# micro_amp.net
KiCad netlist of a schematic drawn in EAGLE
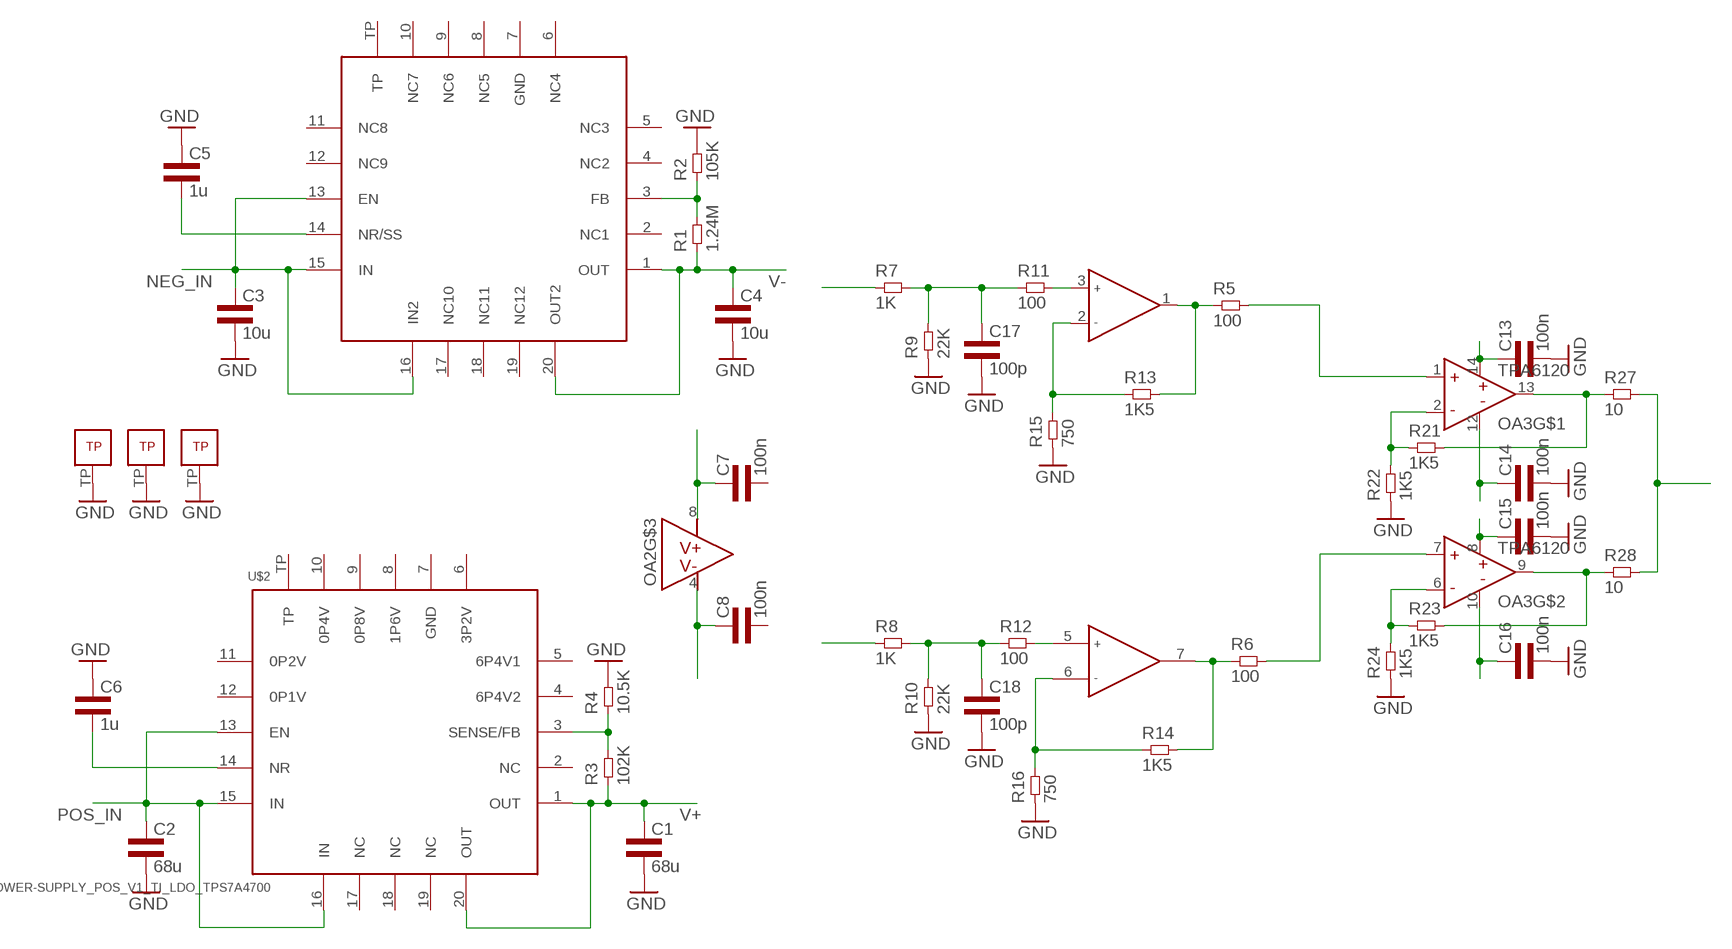
[diagram p0: schematic, sheet 1]

(export (version "E")
  (design (tool "Eeschema 10.0.6"))
  (components
    (comp (ref "C1")
      (value "68u")
      (footprint "eagle-import:1210L3")
      (libsource (lib "eagle-import") (part "CAP1210L3"))
    )
    (comp (ref "C2")
      (value "68u")
      (footprint "eagle-import:1210L3")
      (libsource (lib "eagle-import") (part "CAP1210L3"))
    )
    (comp (ref "C3")
      (value "10u")
      (footprint "eagle-import:0805L3")
      (libsource (lib "eagle-import") (part "CAP0805L3"))
    )
    (comp (ref "C4")
      (value "10u")
      (footprint "eagle-import:0805L3")
      (libsource (lib "eagle-import") (part "CAP0805L3"))
    )
    (comp (ref "C5")
      (value "1u")
      (footprint "eagle-import:0603L3")
      (libsource (lib "eagle-import") (part "CAP0603L3"))
    )
    (comp (ref "C6")
      (value "1u")
      (footprint "eagle-import:0603L3")
      (libsource (lib "eagle-import") (part "CAP0603L3"))
    )
    (comp (ref "C7")
      (value "100n")
      (footprint "eagle-import:0402L3")
      (libsource (lib "eagle-import") (part "CAP0402L3"))
    )
    (comp (ref "C8")
      (value "100n")
      (footprint "eagle-import:0402L3")
      (libsource (lib "eagle-import") (part "CAP0402L3"))
    )
    (comp (ref "C13")
      (value "100n")
      (footprint "eagle-import:0402L3")
      (libsource (lib "eagle-import") (part "CAP0402L3"))
    )
    (comp (ref "C14")
      (value "100n")
      (footprint "eagle-import:0402L3")
      (libsource (lib "eagle-import") (part "CAP0402L3"))
    )
    (comp (ref "C15")
      (value "100n")
      (footprint "eagle-import:0402L3")
      (libsource (lib "eagle-import") (part "CAP0402L3"))
    )
    (comp (ref "C16")
      (value "100n")
      (footprint "eagle-import:0402L3")
      (libsource (lib "eagle-import") (part "CAP0402L3"))
    )
    (comp (ref "C17")
      (value "100p")
      (footprint "eagle-import:0402L3")
      (libsource (lib "eagle-import") (part "CAP0402L3"))
    )
    (comp (ref "C18")
      (value "100p")
      (footprint "eagle-import:0402L3")
      (libsource (lib "eagle-import") (part "CAP0402L3"))
    )
    (comp (ref "OA1")
      (value "TPA6120QFN")
      (footprint "eagle-import:S-PVQFN-N14")
      (libsource (lib "eagle-import") (part "TPA6120QFN"))
    )
    (comp (ref "OA2")
      (value "OPA1612")
      (footprint "eagle-import:S-PWSON-N8")
      (libsource (lib "eagle-import") (part "OPA1612"))
    )
    (comp (ref "OA3")
      (value "TPA6120QFN")
      (footprint "eagle-import:S-PVQFN-N14")
      (libsource (lib "eagle-import") (part "TPA6120QFN"))
    )
    (comp (ref "R1")
      (value "1.24M")
      (footprint "eagle-import:0402L3")
      (libsource (lib "eagle-import") (part "RES0402L3"))
    )
    (comp (ref "R2")
      (value "105K")
      (footprint "eagle-import:0402L3")
      (libsource (lib "eagle-import") (part "RES0402L3"))
    )
    (comp (ref "R3")
      (value "102K")
      (footprint "eagle-import:0402L3")
      (libsource (lib "eagle-import") (part "RES0402L3"))
    )
    (comp (ref "R4")
      (value "10.5K")
      (footprint "eagle-import:0402L3")
      (libsource (lib "eagle-import") (part "RES0402L3"))
    )
    (comp (ref "R5")
      (value "100")
      (footprint "eagle-import:0402L3")
      (libsource (lib "eagle-import") (part "RES0402L3"))
    )
    (comp (ref "R6")
      (value "100")
      (footprint "eagle-import:0402L3")
      (libsource (lib "eagle-import") (part "RES0402L3"))
    )
    (comp (ref "R7")
      (value "1K")
      (footprint "eagle-import:0402L3")
      (libsource (lib "eagle-import") (part "RES0402L3"))
    )
    (comp (ref "R8")
      (value "1K")
      (footprint "eagle-import:0402L3")
      (libsource (lib "eagle-import") (part "RES0402L3"))
    )
    (comp (ref "R9")
      (value "22K")
      (footprint "eagle-import:0402L3")
      (libsource (lib "eagle-import") (part "RES0402L3"))
    )
    (comp (ref "R10")
      (value "22K")
      (footprint "eagle-import:0402L3")
      (libsource (lib "eagle-import") (part "RES0402L3"))
    )
    (comp (ref "R11")
      (value "100")
      (footprint "eagle-import:0402L3")
      (libsource (lib "eagle-import") (part "RES0402L3"))
    )
    (comp (ref "R12")
      (value "100")
      (footprint "eagle-import:0402L3")
      (libsource (lib "eagle-import") (part "RES0402L3"))
    )
    (comp (ref "R13")
      (value "1K5")
      (footprint "eagle-import:0402L3")
      (libsource (lib "eagle-import") (part "RES0402L3"))
    )
    (comp (ref "R14")
      (value "1K5")
      (footprint "eagle-import:0402L3")
      (libsource (lib "eagle-import") (part "RES0402L3"))
    )
    (comp (ref "R15")
      (value "750")
      (footprint "eagle-import:0402L3")
      (libsource (lib "eagle-import") (part "RES0402L3"))
    )
    (comp (ref "R16")
      (value "750")
      (footprint "eagle-import:0402L3")
      (libsource (lib "eagle-import") (part "RES0402L3"))
    )
    (comp (ref "R21")
      (value "1K5")
      (footprint "eagle-import:0402L3")
      (libsource (lib "eagle-import") (part "RES0402L3"))
    )
    (comp (ref "R22")
      (value "1K5")
      (footprint "eagle-import:0402L3")
      (libsource (lib "eagle-import") (part "RES0402L3"))
    )
    (comp (ref "R23")
      (value "1K5")
      (footprint "eagle-import:0402L3")
      (libsource (lib "eagle-import") (part "RES0402L3"))
    )
    (comp (ref "R24")
      (value "1K5")
      (footprint "eagle-import:0402L3")
      (libsource (lib "eagle-import") (part "RES0402L3"))
    )
    (comp (ref "R27")
      (value "10")
      (footprint "eagle-import:0805L3")
      (libsource (lib "eagle-import") (part "RES0805L3"))
    )
    (comp (ref "R28")
      (value "10")
      (footprint "eagle-import:0805L3")
      (libsource (lib "eagle-import") (part "RES0805L3"))
    )
    (comp (ref "U$1")
      (value "POWER-SUPPLY_POS_V1_TI_LDO_TPS7A3301RGWT")
      (footprint "eagle-import:POWER-SUPPLY_POS_V1_TI_LDO_VQFN-20")
      (libsource (lib "eagle-import") (part "POWER-SUPPLY_POS_V1_TI_LDO_TPS7A3301RGWT"))
    )
    (comp (ref "U$2")
      (value "POWER-SUPPLY_POS_V1_TI_LDO_TPS7A4700")
      (footprint "eagle-import:POWER-SUPPLY_POS_V1_TI_LDO_VQFN-20")
      (libsource (lib "eagle-import") (part "POWER-SUPPLY_POS_V1_TI_LDO_TPS7A4700"))
    )
  )
  (nets
    (net (code "1") (name "/NEG_IN") (class "Default")
      (node (ref "C3") (pin "1") (pinfunction "1_1") (pintype "bidirectional"))
      (node (ref "U$1") (pin "13") (pinfunction "EN_13") (pintype "bidirectional"))
      (node (ref "U$1") (pin "15") (pinfunction "IN_15") (pintype "bidirectional"))
      (node (ref "U$1") (pin "16") (pinfunction "IN2_16") (pintype "bidirectional"))
    )
    (net (code "2") (name "/POS_IN") (class "Default")
      (node (ref "C2") (pin "P$1") (pinfunction "1_P$1") (pintype "bidirectional"))
      (node (ref "U$2") (pin "13") (pinfunction "EN_13") (pintype "bidirectional"))
      (node (ref "U$2") (pin "15") (pinfunction "IN_15") (pintype "bidirectional"))
      (node (ref "U$2") (pin "16") (pinfunction "IN_16") (pintype "bidirectional"))
    )
    (net (code "3") (name "/V+") (class "Default")
      (node (ref "C1") (pin "P$1") (pinfunction "1_P$1") (pintype "bidirectional"))
      (node (ref "C13") (pin "P$1") (pinfunction "1_P$1") (pintype "bidirectional"))
      (node (ref "C15") (pin "P$1") (pinfunction "1_P$1") (pintype "bidirectional"))
      (node (ref "C7") (pin "P$1") (pinfunction "1_P$1") (pintype "bidirectional"))
      (node (ref "OA2") (pin "8") (pinfunction "V+_8") (pintype "power_in"))
      (node (ref "OA3") (pin "14") (pinfunction "V+_14") (pintype "bidirectional"))
      (node (ref "OA3") (pin "8") (pinfunction "V+_8") (pintype "bidirectional"))
      (node (ref "R3") (pin "P$1") (pinfunction "1_P$1") (pintype "bidirectional"))
      (node (ref "U$2") (pin "1") (pinfunction "OUT_1") (pintype "bidirectional"))
      (node (ref "U$2") (pin "20") (pinfunction "OUT_20") (pintype "bidirectional"))
    )
    (net (code "4") (name "/V-") (class "Default")
      (node (ref "C14") (pin "P$1") (pinfunction "1_P$1") (pintype "bidirectional"))
      (node (ref "C16") (pin "P$1") (pinfunction "1_P$1") (pintype "bidirectional"))
      (node (ref "C4") (pin "1") (pinfunction "1_1") (pintype "bidirectional"))
      (node (ref "C8") (pin "P$1") (pinfunction "1_P$1") (pintype "bidirectional"))
      (node (ref "OA2") (pin "4") (pinfunction "V-_4") (pintype "power_in"))
      (node (ref "OA3") (pin "10") (pinfunction "V-_10") (pintype "bidirectional"))
      (node (ref "OA3") (pin "12") (pinfunction "V-_12") (pintype "bidirectional"))
      (node (ref "R1") (pin "P$1") (pinfunction "1_P$1") (pintype "bidirectional"))
      (node (ref "U$1") (pin "1") (pinfunction "OUT_1") (pintype "bidirectional"))
      (node (ref "U$1") (pin "20") (pinfunction "OUT2_20") (pintype "bidirectional"))
    )
    (net (code "5") (name "GND") (class "Default")
      (node (ref "C1") (pin "P$2") (pinfunction "2_P$2") (pintype "bidirectional"))
      (node (ref "C13") (pin "P$2") (pinfunction "2_P$2") (pintype "bidirectional"))
      (node (ref "C14") (pin "P$2") (pinfunction "2_P$2") (pintype "bidirectional"))
      (node (ref "C15") (pin "P$2") (pinfunction "2_P$2") (pintype "bidirectional"))
      (node (ref "C16") (pin "P$2") (pinfunction "2_P$2") (pintype "bidirectional"))
      (node (ref "C17") (pin "P$2") (pinfunction "2_P$2") (pintype "bidirectional"))
      (node (ref "C18") (pin "P$2") (pinfunction "2_P$2") (pintype "bidirectional"))
      (node (ref "C2") (pin "P$2") (pinfunction "2_P$2") (pintype "bidirectional"))
      (node (ref "C3") (pin "2") (pinfunction "2_2") (pintype "bidirectional"))
      (node (ref "C4") (pin "2") (pinfunction "2_2") (pintype "bidirectional"))
      (node (ref "C5") (pin "P$1") (pinfunction "1_P$1") (pintype "bidirectional"))
      (node (ref "C6") (pin "P$1") (pinfunction "1_P$1") (pintype "bidirectional"))
      (node (ref "OA1") (pin "TP") (pinfunction "TP_TP") (pintype "bidirectional"))
      (node (ref "OA2") (pin "TP") (pinfunction "TP_TP") (pintype "bidirectional"))
      (node (ref "OA3") (pin "TP") (pinfunction "TP_TP") (pintype "bidirectional"))
      (node (ref "R10") (pin "P$1") (pinfunction "1_P$1") (pintype "bidirectional"))
      (node (ref "R15") (pin "P$1") (pinfunction "1_P$1") (pintype "bidirectional"))
      (node (ref "R16") (pin "P$1") (pinfunction "1_P$1") (pintype "bidirectional"))
      (node (ref "R2") (pin "P$2") (pinfunction "2_P$2") (pintype "bidirectional"))
      (node (ref "R22") (pin "P$1") (pinfunction "1_P$1") (pintype "bidirectional"))
      (node (ref "R24") (pin "P$1") (pinfunction "1_P$1") (pintype "bidirectional"))
      (node (ref "R4") (pin "P$2") (pinfunction "2_P$2") (pintype "bidirectional"))
      (node (ref "R9") (pin "P$1") (pinfunction "1_P$1") (pintype "bidirectional"))
    )
    (net (code "6") (name "Net-(C5-2)") (class "Default")
      (node (ref "C5") (pin "P$2") (pinfunction "2_P$2") (pintype "bidirectional"))
      (node (ref "U$1") (pin "14") (pinfunction "NR/SS_14") (pintype "bidirectional"))
    )
    (net (code "7") (name "Net-(C6-2)") (class "Default")
      (node (ref "C6") (pin "P$2") (pinfunction "2_P$2") (pintype "bidirectional"))
      (node (ref "U$2") (pin "14") (pinfunction "NR_14") (pintype "bidirectional"))
    )
    (net (code "8") (name "Net-(C17-1)") (class "Default")
      (node (ref "C17") (pin "P$1") (pinfunction "1_P$1") (pintype "bidirectional"))
      (node (ref "R11") (pin "P$1") (pinfunction "1_P$1") (pintype "bidirectional"))
      (node (ref "R7") (pin "P$2") (pinfunction "2_P$2") (pintype "bidirectional"))
      (node (ref "R9") (pin "P$2") (pinfunction "2_P$2") (pintype "bidirectional"))
    )
    (net (code "9") (name "Net-(C18-1)") (class "Default")
      (node (ref "C18") (pin "P$1") (pinfunction "1_P$1") (pintype "bidirectional"))
      (node (ref "R10") (pin "P$2") (pinfunction "2_P$2") (pintype "bidirectional"))
      (node (ref "R12") (pin "P$1") (pinfunction "1_P$1") (pintype "bidirectional"))
      (node (ref "R8") (pin "P$2") (pinfunction "2_P$2") (pintype "bidirectional"))
    )
    (net (code "10") (name "Net-(OA2A-INA+)") (class "Default")
      (node (ref "OA2") (pin "3") (pinfunction "INA+_3") (pintype "bidirectional"))
      (node (ref "R11") (pin "P$2") (pinfunction "2_P$2") (pintype "bidirectional"))
    )
    (net (code "11") (name "Net-(OA2A-INA-)") (class "Default")
      (node (ref "OA2") (pin "2") (pinfunction "INA-_2") (pintype "bidirectional"))
      (node (ref "R13") (pin "P$1") (pinfunction "1_P$1") (pintype "bidirectional"))
      (node (ref "R15") (pin "P$2") (pinfunction "2_P$2") (pintype "bidirectional"))
    )
    (net (code "12") (name "Net-(OA2A-OUTA)") (class "Default")
      (node (ref "OA2") (pin "1") (pinfunction "OUTA_1") (pintype "bidirectional"))
      (node (ref "R13") (pin "P$2") (pinfunction "2_P$2") (pintype "bidirectional"))
      (node (ref "R5") (pin "P$1") (pinfunction "1_P$1") (pintype "bidirectional"))
    )
    (net (code "13") (name "Net-(OA2B-INB+)") (class "Default")
      (node (ref "OA2") (pin "5") (pinfunction "INB+_5") (pintype "bidirectional"))
      (node (ref "R12") (pin "P$2") (pinfunction "2_P$2") (pintype "bidirectional"))
    )
    (net (code "14") (name "Net-(OA2B-INB-)") (class "Default")
      (node (ref "OA2") (pin "6") (pinfunction "INB-_6") (pintype "bidirectional"))
      (node (ref "R14") (pin "P$1") (pinfunction "1_P$1") (pintype "bidirectional"))
      (node (ref "R16") (pin "P$2") (pinfunction "2_P$2") (pintype "bidirectional"))
    )
    (net (code "15") (name "Net-(OA2B-OUTB)") (class "Default")
      (node (ref "OA2") (pin "7") (pinfunction "OUTB_7") (pintype "bidirectional"))
      (node (ref "R14") (pin "P$2") (pinfunction "2_P$2") (pintype "bidirectional"))
      (node (ref "R6") (pin "P$1") (pinfunction "1_P$1") (pintype "bidirectional"))
    )
    (net (code "16") (name "Net-(OA3A-IN+)") (class "Default")
      (node (ref "OA3") (pin "1") (pinfunction "IN+_1") (pintype "bidirectional"))
      (node (ref "R5") (pin "P$2") (pinfunction "2_P$2") (pintype "bidirectional"))
    )
    (net (code "17") (name "Net-(OA3A-IN-)") (class "Default")
      (node (ref "OA3") (pin "2") (pinfunction "IN-_2") (pintype "bidirectional"))
      (node (ref "R21") (pin "P$1") (pinfunction "1_P$1") (pintype "bidirectional"))
      (node (ref "R22") (pin "P$2") (pinfunction "2_P$2") (pintype "bidirectional"))
    )
    (net (code "18") (name "Net-(OA3A-OUT)") (class "Default")
      (node (ref "OA3") (pin "13") (pinfunction "OUT_13") (pintype "bidirectional"))
      (node (ref "R21") (pin "P$2") (pinfunction "2_P$2") (pintype "bidirectional"))
      (node (ref "R27") (pin "1") (pinfunction "1_1") (pintype "bidirectional"))
    )
    (net (code "19") (name "Net-(OA3B-IN+)") (class "Default")
      (node (ref "OA3") (pin "7") (pinfunction "IN+_7") (pintype "bidirectional"))
      (node (ref "R6") (pin "P$2") (pinfunction "2_P$2") (pintype "bidirectional"))
    )
    (net (code "20") (name "Net-(OA3B-IN-)") (class "Default")
      (node (ref "OA3") (pin "6") (pinfunction "IN-_6") (pintype "bidirectional"))
      (node (ref "R23") (pin "P$1") (pinfunction "1_P$1") (pintype "bidirectional"))
      (node (ref "R24") (pin "P$2") (pinfunction "2_P$2") (pintype "bidirectional"))
    )
    (net (code "21") (name "Net-(OA3B-OUT)") (class "Default")
      (node (ref "OA3") (pin "9") (pinfunction "OUT_9") (pintype "bidirectional"))
      (node (ref "R23") (pin "P$2") (pinfunction "2_P$2") (pintype "bidirectional"))
      (node (ref "R28") (pin "1") (pinfunction "1_1") (pintype "bidirectional"))
    )
    (net (code "22") (name "Net-(R1-2)") (class "Default")
      (node (ref "R1") (pin "P$2") (pinfunction "2_P$2") (pintype "bidirectional"))
      (node (ref "R2") (pin "P$1") (pinfunction "1_P$1") (pintype "bidirectional"))
      (node (ref "U$1") (pin "3") (pinfunction "FB_3") (pintype "bidirectional"))
    )
    (net (code "23") (name "Net-(R3-2)") (class "Default")
      (node (ref "R3") (pin "P$2") (pinfunction "2_P$2") (pintype "bidirectional"))
      (node (ref "R4") (pin "P$1") (pinfunction "1_P$1") (pintype "bidirectional"))
      (node (ref "U$2") (pin "3") (pinfunction "SENSE/FB_3") (pintype "bidirectional"))
    )
    (net (code "24") (name "Net-(R27-Pad2)") (class "Default")
      (node (ref "R27") (pin "2") (pinfunction "2_2") (pintype "bidirectional"))
      (node (ref "R28") (pin "2") (pinfunction "2_2") (pintype "bidirectional"))
    )
    (net (code "25") (name "unconnected-(C7-2-PadP$2)") (class "Default")
      (node (ref "C7") (pin "P$2") (pinfunction "2_P$2") (pintype "bidirectional"))
    )
    (net (code "26") (name "unconnected-(C8-2-PadP$2)") (class "Default")
      (node (ref "C8") (pin "P$2") (pinfunction "2_P$2") (pintype "bidirectional"))
    )
    (net (code "27") (name "unconnected-(R7-1-PadP$1)") (class "Default")
      (node (ref "R7") (pin "P$1") (pinfunction "1_P$1") (pintype "bidirectional"))
    )
    (net (code "28") (name "unconnected-(R8-1-PadP$1)") (class "Default")
      (node (ref "R8") (pin "P$1") (pinfunction "1_P$1") (pintype "bidirectional"))
    )
    (net (code "29") (name "unconnected-(U$1-GND-Pad7)") (class "Default")
      (node (ref "U$1") (pin "7") (pinfunction "GND_7") (pintype "bidirectional"))
    )
    (net (code "30") (name "unconnected-(U$1-NC1-Pad2)") (class "Default")
      (node (ref "U$1") (pin "2") (pinfunction "NC1_2") (pintype "bidirectional"))
    )
    (net (code "31") (name "unconnected-(U$1-NC2-Pad4)") (class "Default")
      (node (ref "U$1") (pin "4") (pinfunction "NC2_4") (pintype "bidirectional"))
    )
    (net (code "32") (name "unconnected-(U$1-NC3-Pad5)") (class "Default")
      (node (ref "U$1") (pin "5") (pinfunction "NC3_5") (pintype "bidirectional"))
    )
    (net (code "33") (name "unconnected-(U$1-NC4-Pad6)") (class "Default")
      (node (ref "U$1") (pin "6") (pinfunction "NC4_6") (pintype "bidirectional"))
    )
    (net (code "34") (name "unconnected-(U$1-NC5-Pad8)") (class "Default")
      (node (ref "U$1") (pin "8") (pinfunction "NC5_8") (pintype "bidirectional"))
    )
    (net (code "35") (name "unconnected-(U$1-NC6-Pad9)") (class "Default")
      (node (ref "U$1") (pin "9") (pinfunction "NC6_9") (pintype "bidirectional"))
    )
    (net (code "36") (name "unconnected-(U$1-NC7-Pad10)") (class "Default")
      (node (ref "U$1") (pin "10") (pinfunction "NC7_10") (pintype "bidirectional"))
    )
    (net (code "37") (name "unconnected-(U$1-NC8-Pad11)") (class "Default")
      (node (ref "U$1") (pin "11") (pinfunction "NC8_11") (pintype "bidirectional"))
    )
    (net (code "38") (name "unconnected-(U$1-NC9-Pad12)") (class "Default")
      (node (ref "U$1") (pin "12") (pinfunction "NC9_12") (pintype "bidirectional"))
    )
    (net (code "39") (name "unconnected-(U$1-NC10-Pad17)") (class "Default")
      (node (ref "U$1") (pin "17") (pinfunction "NC10_17") (pintype "bidirectional"))
    )
    (net (code "40") (name "unconnected-(U$1-NC11-Pad18)") (class "Default")
      (node (ref "U$1") (pin "18") (pinfunction "NC11_18") (pintype "bidirectional"))
    )
    (net (code "41") (name "unconnected-(U$1-NC12-Pad19)") (class "Default")
      (node (ref "U$1") (pin "19") (pinfunction "NC12_19") (pintype "bidirectional"))
    )
    (net (code "42") (name "unconnected-(U$1-PadTP)") (class "Default")
      (node (ref "U$1") (pin "TP") (pinfunction "TP_TP") (pintype "bidirectional"))
    )
    (net (code "43") (name "unconnected-(U$2-0P1V-Pad12)") (class "Default")
      (node (ref "U$2") (pin "12") (pinfunction "0P1V_12") (pintype "bidirectional"))
    )
    (net (code "44") (name "unconnected-(U$2-0P2V-Pad11)") (class "Default")
      (node (ref "U$2") (pin "11") (pinfunction "0P2V_11") (pintype "bidirectional"))
    )
    (net (code "45") (name "unconnected-(U$2-0P4V-Pad10)") (class "Default")
      (node (ref "U$2") (pin "10") (pinfunction "0P4V_10") (pintype "bidirectional"))
    )
    (net (code "46") (name "unconnected-(U$2-0P8V-Pad9)") (class "Default")
      (node (ref "U$2") (pin "9") (pinfunction "0P8V_9") (pintype "bidirectional"))
    )
    (net (code "47") (name "unconnected-(U$2-1P6V-Pad8)") (class "Default")
      (node (ref "U$2") (pin "8") (pinfunction "1P6V_8") (pintype "bidirectional"))
    )
    (net (code "48") (name "unconnected-(U$2-3P2V-Pad6)") (class "Default")
      (node (ref "U$2") (pin "6") (pinfunction "3P2V_6") (pintype "bidirectional"))
    )
    (net (code "49") (name "unconnected-(U$2-6P4V1-Pad5)") (class "Default")
      (node (ref "U$2") (pin "5") (pinfunction "6P4V1_5") (pintype "bidirectional"))
    )
    (net (code "50") (name "unconnected-(U$2-6P4V2-Pad4)") (class "Default")
      (node (ref "U$2") (pin "4") (pinfunction "6P4V2_4") (pintype "bidirectional"))
    )
    (net (code "51") (name "unconnected-(U$2-GND-Pad7)") (class "Default")
      (node (ref "U$2") (pin "7") (pinfunction "GND_7") (pintype "bidirectional"))
    )
    (net (code "52") (name "unconnected-(U$2-NC-Pad2)") (class "Default")
      (node (ref "U$2") (pin "2") (pinfunction "NC_2") (pintype "bidirectional"))
    )
    (net (code "53") (name "unconnected-(U$2-NC-Pad17)") (class "Default")
      (node (ref "U$2") (pin "17") (pinfunction "NC_17") (pintype "bidirectional"))
    )
    (net (code "54") (name "unconnected-(U$2-NC-Pad18)") (class "Default")
      (node (ref "U$2") (pin "18") (pinfunction "NC_18") (pintype "bidirectional"))
    )
    (net (code "55") (name "unconnected-(U$2-NC-Pad19)") (class "Default")
      (node (ref "U$2") (pin "19") (pinfunction "NC_19") (pintype "bidirectional"))
    )
    (net (code "56") (name "unconnected-(U$2-PadTP)") (class "Default")
      (node (ref "U$2") (pin "TP") (pinfunction "TP_TP") (pintype "bidirectional"))
    )
  )
)
